# MCU_64.net
KiCad netlist of a schematic drawn in Altium Designer
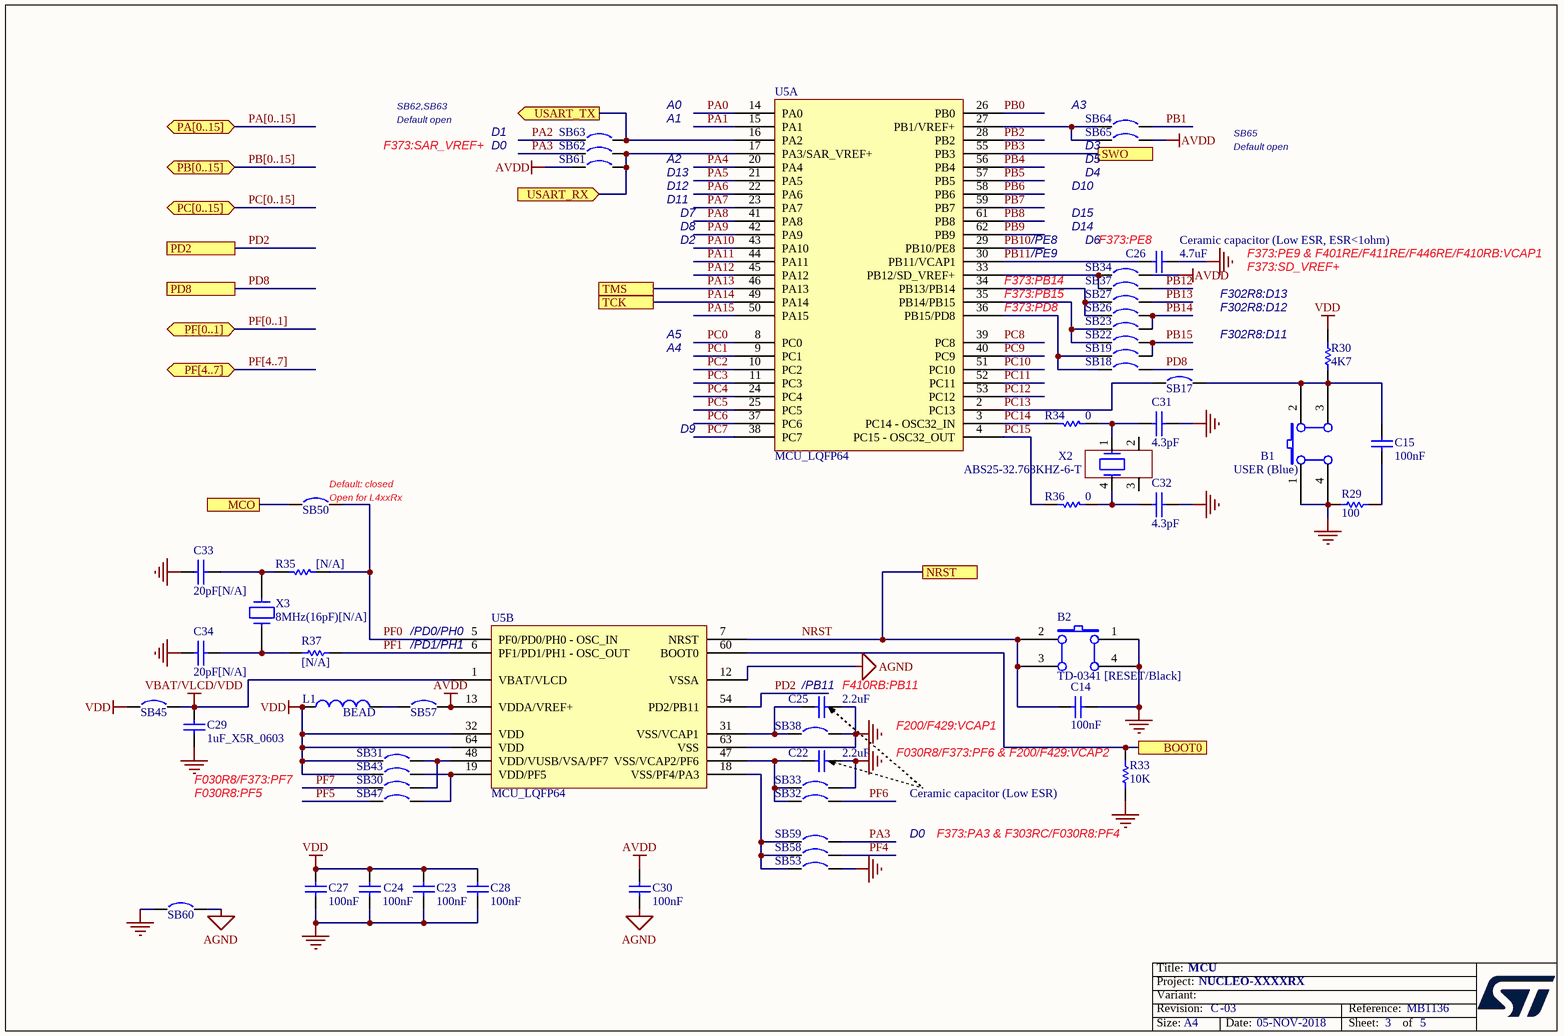
[diagram p0: MCU_64.SchDoc]

(export (version "E")
  (design (tool "Eeschema 10.0.6"))
  (components
    (comp (ref "B1")
      (value "USER (Blue)")
      (footprint "PB10")
      (description "SE PUSHBUTTON")
      (libsource (lib "Documents") (part "SW PUSHBUTTON"))
    )
    (comp (ref "B2")
      (value "TD-0341 [RESET/Black]")
      (footprint "PB10")
      (description "SE PUSHBUTTON")
      (libsource (lib "Documents") (part "SW PUSHBUTTON"))
    )
    (comp (ref "C14")
      (value "100nF")
      (footprint "0603C")
      (description "Capacitor")
      (fields (field (name "PUBLISHER") "Altium Limited"))
      (libsource (lib "Miscellaneous Devices") (part "CAP"))
    )
    (comp (ref "C15")
      (value "100nF")
      (footprint "0603C")
      (description "Capacitor")
      (fields (field (name "PUBLISHER") "Altium Limited"))
      (libsource (lib "Miscellaneous Devices") (part "CAP"))
    )
    (comp (ref "C22")
      (value "2.2uF")
      (footprint "TAN-A")
      (description "Capacitor,2.2uF,16V, X7R,10%,0805,YAGEO")
      (libsource (lib "MCD_TOOLS") (part "Cap_2.2uF_X7R_10%_0805"))
    )
    (comp (ref "C23")
      (value "100nF")
      (footprint "0603C")
      (description "Capacitor")
      (fields (field (name "PUBLISHER") "Altium Limited"))
      (libsource (lib "Miscellaneous Devices") (part "Cap"))
    )
    (comp (ref "C24")
      (value "100nF")
      (footprint "0603C")
      (description "Capacitor")
      (fields (field (name "PUBLISHER") "Altium Limited"))
      (libsource (lib "Miscellaneous Devices") (part "Cap"))
    )
    (comp (ref "C25")
      (value "2.2uF")
      (footprint "TAN-A")
      (description "Capacitor,2.2uF,16V, X7R,10%,0805,YAGEO")
      (libsource (lib "MCD_TOOLS") (part "Cap_2.2uF_X7R_10%_0805"))
    )
    (comp (ref "C26")
      (value "4.7uF")
      (footprint "TAN-A")
      (description "Capacitor,4.7uF,25V, X7R,10%,1206,YAGEO")
      (libsource (lib "MCD_TOOLS") (part "Cap_2.2uF_X7R_10%_0805"))
    )
    (comp (ref "C27")
      (value "100nF")
      (footprint "0603C")
      (description "Capacitor")
      (fields (field (name "PUBLISHER") "Altium Limited"))
      (libsource (lib "Miscellaneous Devices") (part "Cap"))
    )
    (comp (ref "C28")
      (value "100nF")
      (footprint "0603C")
      (description "Capacitor")
      (fields (field (name "PUBLISHER") "Altium Limited"))
      (libsource (lib "Miscellaneous Devices") (part "Cap"))
    )
    (comp (ref "C29")
      (value "1uF_X5R_0603")
      (footprint "0603C")
      (description "0603  X5R 1µF")
      (fields (field (name "TOLERANCE") "10%"))
      (libsource (lib "MB963_1") (part "CAP SMD 0603  X5R 1µF 25V 10%"))
    )
    (comp (ref "C30")
      (value "100nF")
      (footprint "0603C")
      (description "Capacitor")
      (fields (field (name "PUBLISHER") "Altium Limited"))
      (libsource (lib "Miscellaneous Devices") (part "Cap"))
    )
    (comp (ref "C31")
      (value "4.3pF")
      (footprint "0603C")
      (description "Capacitor")
      (libsource (lib "") (part "CAP_1"))
    )
    (comp (ref "C32")
      (value "4.3pF")
      (footprint "0603C")
      (description "Capacitor")
      (libsource (lib "") (part "CAP_1"))
    )
    (comp (ref "C33")
      (value "20pF[N/A]")
      (footprint "0603C")
      (description "Capacitor")
      (libsource (lib "*") (part "CAP"))
    )
    (comp (ref "C34")
      (value "20pF[N/A]")
      (footprint "0603C")
      (description "Capacitor")
      (libsource (lib "*") (part "CAP"))
    )
    (comp (ref "L1")
      (value "BEAD")
      (footprint "0603L")
      (description "Inductor")
      (fields (field (name "PUBLISHER") "Altium Limited"))
      (libsource (lib "Miscellaneous Devices") (part "Inductor"))
    )
    (comp (ref "R29")
      (value "100")
      (footprint "0603R")
      (description "Resistor")
      (fields (field (name "PUBLISHER") "Altium Limited"))
      (libsource (lib "Miscellaneous Devices") (part "Res1"))
    )
    (comp (ref "R30")
      (value "4K7")
      (footprint "0603R")
      (description "Resistor")
      (fields (field (name "PUBLISHER") "Altium Limited"))
      (libsource (lib "Miscellaneous Devices") (part "res1"))
    )
    (comp (ref "R33")
      (value "10K")
      (footprint "0603R")
      (description "Resistor")
      (fields (field (name "PUBLISHER") "Altium Limited"))
      (libsource (lib "Miscellaneous Devices") (part "res1"))
    )
    (comp (ref "R34")
      (value "0")
      (footprint "0603R")
      (description "Resistor")
      (fields (field (name "PUBLISHER") "Altium Limited"))
      (libsource (lib "") (part "Res1_1"))
    )
    (comp (ref "R35")
      (value "[N/A]")
      (footprint "0603R")
      (description "Resistor")
      (fields (field (name "PUBLISHER") "Altium Limited"))
      (libsource (lib "") (part "Res1_1"))
    )
    (comp (ref "R36")
      (value "0")
      (footprint "0603R")
      (description "Resistor")
      (fields (field (name "PUBLISHER") "Altium Limited"))
      (libsource (lib "") (part "Res1_1"))
    )
    (comp (ref "R37")
      (value "[N/A]")
      (footprint "0603R")
      (description "Resistor")
      (fields (field (name "PUBLISHER") "Altium Limited"))
      (libsource (lib "Miscellaneous Devices") (part "Res1"))
    )
    (comp (ref "SB17")
      (value "Circuit Breaker")
      (footprint "JP2_SMD")
      (fields (field (name "PUBLISHER") "Altium Limited"))
      (libsource (lib "MCD_TOOLS") (part "Circuit Breaker"))
    )
    (comp (ref "SB18")
      (value "Circuit Breaker")
      (footprint "JP2_SMD")
      (fields (field (name "PUBLISHER") "Altium Limited"))
      (libsource (lib "MCD_TOOLS") (part "Circuit Breaker"))
    )
    (comp (ref "SB19")
      (value "Circuit Breaker")
      (footprint "JP2_SMD")
      (fields (field (name "PUBLISHER") "Altium Limited"))
      (libsource (lib "MCD_TOOLS") (part "Circuit Breaker"))
    )
    (comp (ref "SB22")
      (value "Circuit Breaker")
      (footprint "JP2_SMD")
      (fields (field (name "PUBLISHER") "Altium Limited"))
      (libsource (lib "MCD_TOOLS") (part "Circuit Breaker"))
    )
    (comp (ref "SB23")
      (value "Circuit Breaker")
      (footprint "JP2_SMD")
      (fields (field (name "PUBLISHER") "Altium Limited"))
      (libsource (lib "MCD_TOOLS") (part "Circuit Breaker"))
    )
    (comp (ref "SB26")
      (value "Circuit Breaker")
      (footprint "JP2_SMD")
      (fields (field (name "PUBLISHER") "Altium Limited"))
      (libsource (lib "MCD_TOOLS") (part "Circuit Breaker"))
    )
    (comp (ref "SB27")
      (value "Circuit Breaker")
      (footprint "JP2_SMD")
      (fields (field (name "PUBLISHER") "Altium Limited"))
      (libsource (lib "MCD_TOOLS") (part "Circuit Breaker"))
    )
    (comp (ref "SB30")
      (value "Circuit Breaker")
      (footprint "JP2_SMD")
      (fields (field (name "PUBLISHER") "Altium Limited"))
      (libsource (lib "MCD_TOOLS") (part "Circuit Breaker"))
    )
    (comp (ref "SB31")
      (value "Circuit Breaker")
      (footprint "JP2_SMD")
      (fields (field (name "PUBLISHER") "Altium Limited"))
      (libsource (lib "MCD_TOOLS") (part "Circuit Breaker"))
    )
    (comp (ref "SB32")
      (value "Circuit Breaker")
      (footprint "JP2_SMD")
      (fields (field (name "PUBLISHER") "Altium Limited"))
      (libsource (lib "MCD_TOOLS") (part "Circuit Breaker"))
    )
    (comp (ref "SB33")
      (value "Circuit Breaker")
      (footprint "JP2_SMD")
      (fields (field (name "PUBLISHER") "Altium Limited"))
      (libsource (lib "MCD_TOOLS") (part "Circuit Breaker"))
    )
    (comp (ref "SB34")
      (value "Circuit Breaker")
      (footprint "JP2_SMD")
      (fields (field (name "PUBLISHER") "Altium Limited"))
      (libsource (lib "MCD_TOOLS") (part "Circuit Breaker"))
    )
    (comp (ref "SB37")
      (value "Circuit Breaker")
      (footprint "JP2_SMD")
      (fields (field (name "PUBLISHER") "Altium Limited"))
      (libsource (lib "MCD_TOOLS") (part "Circuit Breaker"))
    )
    (comp (ref "SB38")
      (value "Circuit Breaker")
      (footprint "JP2_SMD")
      (fields (field (name "PUBLISHER") "Altium Limited"))
      (libsource (lib "MCD_TOOLS") (part "Circuit Breaker"))
    )
    (comp (ref "SB43")
      (value "Circuit Breaker")
      (footprint "JP2_SMD")
      (fields (field (name "PUBLISHER") "Altium Limited"))
      (libsource (lib "MCD_TOOLS") (part "Circuit Breaker"))
    )
    (comp (ref "SB45")
      (value "Circuit Breaker")
      (footprint "JP2_SMD")
      (fields (field (name "PUBLISHER") "Altium Limited"))
      (libsource (lib "MCD_TOOLS") (part "Circuit Breaker"))
    )
    (comp (ref "SB47")
      (value "Circuit Breaker")
      (footprint "JP2_SMD")
      (fields (field (name "PUBLISHER") "Altium Limited"))
      (libsource (lib "MCD_TOOLS") (part "Circuit Breaker"))
    )
    (comp (ref "SB50")
      (value "Circuit Breaker")
      (footprint "JP2_SMD")
      (fields (field (name "PUBLISHER") "Altium Limited"))
      (libsource (lib "MCD_TOOLS") (part "Circuit Breaker"))
    )
    (comp (ref "SB53")
      (value "Circuit Breaker")
      (footprint "JP2_SMD")
      (fields (field (name "PUBLISHER") "Altium Limited"))
      (libsource (lib "MCD_TOOLS") (part "Circuit Breaker"))
    )
    (comp (ref "SB57")
      (value "Circuit Breaker")
      (footprint "JP2_SMD")
      (fields (field (name "PUBLISHER") "Altium Limited"))
      (libsource (lib "MCD_TOOLS") (part "Circuit Breaker"))
    )
    (comp (ref "SB58")
      (value "Circuit Breaker")
      (footprint "JP2_SMD")
      (fields (field (name "PUBLISHER") "Altium Limited"))
      (libsource (lib "MCD_TOOLS") (part "Circuit Breaker"))
    )
    (comp (ref "SB59")
      (value "Circuit Breaker")
      (footprint "JP2_SMD")
      (fields (field (name "PUBLISHER") "Altium Limited"))
      (libsource (lib "MCD_TOOLS") (part "Circuit Breaker"))
    )
    (comp (ref "SB60")
      (value "Circuit Breaker")
      (footprint "JP2_SMD")
      (fields (field (name "PUBLISHER") "Altium Limited"))
      (libsource (lib "MCD_TOOLS") (part "Circuit Breaker"))
    )
    (comp (ref "SB61")
      (value "Circuit Breaker")
      (footprint "JP2_SMD")
      (fields (field (name "PUBLISHER") "Altium Limited"))
      (libsource (lib "MCD_TOOLS") (part "Circuit Breaker"))
    )
    (comp (ref "SB62")
      (value "Circuit Breaker")
      (footprint "JP2_SMD")
      (fields (field (name "PUBLISHER") "Altium Limited"))
      (libsource (lib "MCD_TOOLS") (part "Circuit Breaker"))
    )
    (comp (ref "SB63")
      (value "Circuit Breaker")
      (footprint "JP2_SMD")
      (fields (field (name "PUBLISHER") "Altium Limited"))
      (libsource (lib "MCD_TOOLS") (part "Circuit Breaker"))
    )
    (comp (ref "SB64")
      (value "Circuit Breaker")
      (footprint "JP2_SMD")
      (fields (field (name "PUBLISHER") "Altium Limited"))
      (libsource (lib "MCD_TOOLS") (part "Circuit Breaker"))
    )
    (comp (ref "SB65")
      (value "Circuit Breaker")
      (footprint "JP2_SMD")
      (fields (field (name "PUBLISHER") "Altium Limited"))
      (libsource (lib "MCD_TOOLS") (part "Circuit Breaker"))
    )
    (comp (ref "U5") (value "MCU_LQFP64") (footprint "LQFP64") (libsource (lib "MB1136") (part "MCU_LQFP64")))
    (comp (ref "X2")
      (value "ABS25-32.768KHZ-6-T")
      (footprint "XTAL_4SM_8X3R8")
      (libsource (lib "*") (part "MC306"))
    )
    (comp (ref "X3")
      (value "8MHz(16pF)[N/A]")
      (footprint "XTAL1")
      (description "Crystal")
      (libsource (lib "*") (part "CRYSTAL"))
    )
  )
  (nets
    (net (code "1") (name "/BOOT0") (class "Default")
      (node (ref "R33") (pin "1") (pinfunction "1_1") (pintype "passive"))
      (node (ref "U5") (pin "60") (pinfunction "BOOT0_60") (pintype "passive"))
    )
    (net (code "2") (name "/MCO") (class "Default")
      (node (ref "SB50") (pin "1") (pinfunction "1_1") (pintype "passive"))
    )
    (net (code "3") (name "/NRST") (class "Default")
      (node (ref "B2") (pin "2") (pinfunction "B0_2") (pintype "passive"))
      (node (ref "B2") (pin "3") (pinfunction "B1_3") (pintype "passive"))
      (node (ref "C14") (pin "2") (pinfunction "2_2") (pintype "passive"))
      (node (ref "U5") (pin "7") (pinfunction "NRST_7") (pintype "passive"))
    )
    (net (code "4") (name "/PA0") (class "Default")
      (node (ref "U5") (pin "14") (pinfunction "PA0_14") (pintype "passive"))
    )
    (net (code "5") (name "/PA1") (class "Default")
      (node (ref "U5") (pin "15") (pinfunction "PA1_15") (pintype "passive"))
    )
    (net (code "6") (name "/PA2") (class "Default")
      (node (ref "SB63") (pin "1") (pinfunction "1_1") (pintype "passive"))
    )
    (net (code "7") (name "/PA3") (class "Default")
      (node (ref "SB59") (pin "2") (pinfunction "2_2") (pintype "passive"))
      (node (ref "SB62") (pin "1") (pinfunction "1_1") (pintype "passive"))
    )
    (net (code "8") (name "/PA4") (class "Default")
      (node (ref "U5") (pin "20") (pinfunction "PA4_20") (pintype "passive"))
    )
    (net (code "9") (name "/PA5") (class "Default")
      (node (ref "U5") (pin "21") (pinfunction "PA5_21") (pintype "passive"))
    )
    (net (code "10") (name "/PA6") (class "Default")
      (node (ref "U5") (pin "22") (pinfunction "PA6_22") (pintype "passive"))
    )
    (net (code "11") (name "/PA7") (class "Default")
      (node (ref "U5") (pin "23") (pinfunction "PA7_23") (pintype "passive"))
    )
    (net (code "12") (name "/PA8") (class "Default")
      (node (ref "U5") (pin "41") (pinfunction "PA8_41") (pintype "passive"))
    )
    (net (code "13") (name "/PA9") (class "Default")
      (node (ref "U5") (pin "42") (pinfunction "PA9_42") (pintype "passive"))
    )
    (net (code "14") (name "/PA10") (class "Default")
      (node (ref "U5") (pin "43") (pinfunction "PA10_43") (pintype "passive"))
    )
    (net (code "15") (name "/PA11") (class "Default")
      (node (ref "U5") (pin "44") (pinfunction "PA11_44") (pintype "passive"))
    )
    (net (code "16") (name "/PA12") (class "Default")
      (node (ref "U5") (pin "45") (pinfunction "PA12_45") (pintype "passive"))
    )
    (net (code "17") (name "/PA13") (class "Default")
      (node (ref "U5") (pin "46") (pinfunction "PA13_46") (pintype "passive"))
    )
    (net (code "18") (name "/PA14") (class "Default")
      (node (ref "U5") (pin "49") (pinfunction "PA14_49") (pintype "passive"))
    )
    (net (code "19") (name "/PA15") (class "Default")
      (node (ref "U5") (pin "50") (pinfunction "PA15_50") (pintype "passive"))
    )
    (net (code "21") (name "/PB0") (class "Default")
      (node (ref "U5") (pin "26") (pinfunction "PB0_26") (pintype "passive"))
    )
    (net (code "22") (name "/PB1") (class "Default")
      (node (ref "SB64") (pin "2") (pinfunction "2_2") (pintype "passive"))
    )
    (net (code "23") (name "/PB2") (class "Default")
      (node (ref "U5") (pin "28") (pinfunction "PB2_28") (pintype "passive"))
    )
    (net (code "24") (name "/PB3") (class "Default")
      (node (ref "U5") (pin "55") (pinfunction "PB3_55") (pintype "passive"))
    )
    (net (code "25") (name "/PB4") (class "Default")
      (node (ref "U5") (pin "56") (pinfunction "PB4_56") (pintype "passive"))
    )
    (net (code "26") (name "/PB5") (class "Default")
      (node (ref "U5") (pin "57") (pinfunction "PB5_57") (pintype "passive"))
    )
    (net (code "27") (name "/PB6") (class "Default")
      (node (ref "U5") (pin "58") (pinfunction "PB6_58") (pintype "passive"))
    )
    (net (code "28") (name "/PB7") (class "Default")
      (node (ref "U5") (pin "59") (pinfunction "PB7_59") (pintype "passive"))
    )
    (net (code "29") (name "/PB8") (class "Default")
      (node (ref "U5") (pin "61") (pinfunction "PB8_61") (pintype "passive"))
    )
    (net (code "30") (name "/PB9") (class "Default")
      (node (ref "U5") (pin "62") (pinfunction "PB9_62") (pintype "passive"))
    )
    (net (code "31") (name "/PB10") (class "Default")
      (node (ref "U5") (pin "29") (pinfunction "PB10/PE8_29") (pintype "passive"))
    )
    (net (code "32") (name "/PB11") (class "Default")
      (node (ref "C26") (pin "1") (pinfunction "1_1") (pintype "passive"))
      (node (ref "U5") (pin "30") (pinfunction "PB11/VCAP1_30") (pintype "passive"))
    )
    (net (code "33") (name "/PB12") (class "Default")
      (node (ref "SB37") (pin "2") (pinfunction "2_2") (pintype "passive"))
    )
    (net (code "34") (name "/PB13") (class "Default")
      (node (ref "SB27") (pin "2") (pinfunction "2_2") (pintype "passive"))
    )
    (net (code "35") (name "/PB14") (class "Default")
      (node (ref "SB23") (pin "2") (pinfunction "2_2") (pintype "passive"))
      (node (ref "SB26") (pin "2") (pinfunction "2_2") (pintype "passive"))
    )
    (net (code "36") (name "/PB15") (class "Default")
      (node (ref "SB19") (pin "2") (pinfunction "2_2") (pintype "passive"))
      (node (ref "SB22") (pin "2") (pinfunction "2_2") (pintype "passive"))
    )
    (net (code "38") (name "/PC0") (class "Default")
      (node (ref "U5") (pin "8") (pinfunction "PC0_8") (pintype "passive"))
    )
    (net (code "39") (name "/PC1") (class "Default")
      (node (ref "U5") (pin "9") (pinfunction "PC1_9") (pintype "passive"))
    )
    (net (code "40") (name "/PC2") (class "Default")
      (node (ref "U5") (pin "10") (pinfunction "PC2_10") (pintype "passive"))
    )
    (net (code "41") (name "/PC3") (class "Default")
      (node (ref "U5") (pin "11") (pinfunction "PC3_11") (pintype "passive"))
    )
    (net (code "42") (name "/PC4") (class "Default")
      (node (ref "U5") (pin "24") (pinfunction "PC4_24") (pintype "passive"))
    )
    (net (code "43") (name "/PC5") (class "Default")
      (node (ref "U5") (pin "25") (pinfunction "PC5_25") (pintype "passive"))
    )
    (net (code "44") (name "/PC6") (class "Default")
      (node (ref "U5") (pin "37") (pinfunction "PC6_37") (pintype "passive"))
    )
    (net (code "45") (name "/PC7") (class "Default")
      (node (ref "U5") (pin "38") (pinfunction "PC7_38") (pintype "passive"))
    )
    (net (code "46") (name "/PC8") (class "Default")
      (node (ref "U5") (pin "39") (pinfunction "PC8_39") (pintype "passive"))
    )
    (net (code "47") (name "/PC9") (class "Default")
      (node (ref "U5") (pin "40") (pinfunction "PC9_40") (pintype "passive"))
    )
    (net (code "48") (name "/PC10") (class "Default")
      (node (ref "U5") (pin "51") (pinfunction "PC10_51") (pintype "passive"))
    )
    (net (code "49") (name "/PC11") (class "Default")
      (node (ref "U5") (pin "52") (pinfunction "PC11_52") (pintype "passive"))
    )
    (net (code "50") (name "/PC12") (class "Default")
      (node (ref "U5") (pin "53") (pinfunction "PC12_53") (pintype "passive"))
    )
    (net (code "51") (name "/PC13") (class "Default")
      (node (ref "SB17") (pin "1") (pinfunction "1_1") (pintype "passive"))
      (node (ref "U5") (pin "2") (pinfunction "PC13_2") (pintype "passive"))
    )
    (net (code "52") (name "/PC14") (class "Default")
      (node (ref "R34") (pin "2") (pinfunction "2_2") (pintype "passive"))
      (node (ref "U5") (pin "3") (pinfunction "PC14_-_OSC32_IN_3") (pintype "passive"))
    )
    (net (code "53") (name "/PC15") (class "Default")
      (node (ref "R36") (pin "2") (pinfunction "2_2") (pintype "passive"))
      (node (ref "U5") (pin "4") (pinfunction "PC15_-_OSC32_OUT_4") (pintype "passive"))
    )
    (net (code "55") (name "/PD2") (class "Default")
      (node (ref "U5") (pin "54") (pinfunction "PD2/PB11_54") (pintype "passive"))
    )
    (net (code "56") (name "/PD8") (class "Default")
      (node (ref "SB18") (pin "2") (pinfunction "2_2") (pintype "passive"))
    )
    (net (code "57") (name "/PF0") (class "Default")
      (node (ref "R35") (pin "1") (pinfunction "1_1") (pintype "passive"))
      (node (ref "SB50") (pin "2") (pinfunction "2_2") (pintype "passive"))
      (node (ref "U5") (pin "5") (pinfunction "PF0/PD0/PH0_-_OSC_IN_5") (pintype "passive"))
    )
    (net (code "58") (name "/PF1") (class "Default")
      (node (ref "R37") (pin "1") (pinfunction "1_1") (pintype "passive"))
      (node (ref "U5") (pin "6") (pinfunction "PF1/PD1/PH1_-_OSC_OUT_6") (pintype "passive"))
    )
    (net (code "59") (name "/PF4") (class "Default")
      (node (ref "SB58") (pin "2") (pinfunction "2_2") (pintype "passive"))
    )
    (net (code "60") (name "/PF5") (class "Default")
      (node (ref "SB47") (pin "1") (pinfunction "1_1") (pintype "passive"))
    )
    (net (code "61") (name "/PF6") (class "Default")
      (node (ref "SB32") (pin "2") (pinfunction "2_2") (pintype "passive"))
    )
    (net (code "62") (name "/PF7") (class "Default")
      (node (ref "SB30") (pin "1") (pinfunction "1_1") (pintype "passive"))
    )
    (net (code "65") (name "/USART_RX") (class "Default")
      (node (ref "SB61") (pin "2") (pinfunction "2_2") (pintype "passive"))
      (node (ref "SB62") (pin "2") (pinfunction "2_2") (pintype "passive"))
      (node (ref "U5") (pin "17") (pinfunction "PA3/SAR_VREF+_17") (pintype "passive"))
    )
    (net (code "66") (name "/USART_TX") (class "Default")
      (node (ref "SB63") (pin "2") (pinfunction "2_2") (pintype "passive"))
      (node (ref "U5") (pin "16") (pinfunction "PA2_16") (pintype "passive"))
    )
    (net (code "67") (name "AGND") (class "Default")
      (node (ref "C30") (pin "2") (pinfunction "2_2") (pintype "passive"))
      (node (ref "SB60") (pin "2") (pinfunction "2_2") (pintype "passive"))
      (node (ref "U5") (pin "12") (pinfunction "VSSA_12") (pintype "passive"))
    )
    (net (code "68") (name "AVDD") (class "Default")
      (node (ref "C30") (pin "1") (pinfunction "1_1") (pintype "passive"))
      (node (ref "SB34") (pin "2") (pinfunction "2_2") (pintype "passive"))
      (node (ref "SB57") (pin "2") (pinfunction "2_2") (pintype "passive"))
      (node (ref "SB61") (pin "1") (pinfunction "1_1") (pintype "passive"))
      (node (ref "SB65") (pin "2") (pinfunction "2_2") (pintype "passive"))
      (node (ref "U5") (pin "13") (pinfunction "VDDA/VREF+_13") (pintype "passive"))
    )
    (net (code "69") (name "GND") (class "Default")
      (node (ref "B1") (pin "1") (pinfunction "A0_1") (pintype "passive"))
      (node (ref "B1") (pin "4") (pinfunction "A1_4") (pintype "passive"))
      (node (ref "B2") (pin "1") (pinfunction "A0_1") (pintype "passive"))
      (node (ref "B2") (pin "4") (pinfunction "A1_4") (pintype "passive"))
      (node (ref "C14") (pin "1") (pinfunction "1_1") (pintype "passive"))
      (node (ref "C22") (pin "2") (pinfunction "2_2") (pintype "passive"))
      (node (ref "C23") (pin "2") (pinfunction "2_2") (pintype "passive"))
      (node (ref "C24") (pin "2") (pinfunction "2_2") (pintype "passive"))
      (node (ref "C25") (pin "2") (pinfunction "2_2") (pintype "passive"))
      (node (ref "C26") (pin "2") (pinfunction "2_2") (pintype "passive"))
      (node (ref "C27") (pin "2") (pinfunction "2_2") (pintype "passive"))
      (node (ref "C28") (pin "2") (pinfunction "2_2") (pintype "passive"))
      (node (ref "C29") (pin "2") (pinfunction "2_2") (pintype "passive"))
      (node (ref "C31") (pin "2") (pinfunction "2_2") (pintype "passive"))
      (node (ref "C32") (pin "2") (pinfunction "2_2") (pintype "passive"))
      (node (ref "C33") (pin "2") (pinfunction "2_2") (pintype "passive"))
      (node (ref "C34") (pin "2") (pinfunction "2_2") (pintype "passive"))
      (node (ref "R29") (pin "1") (pinfunction "1_1") (pintype "passive"))
      (node (ref "R33") (pin "2") (pinfunction "2_2") (pintype "passive"))
      (node (ref "SB33") (pin "2") (pinfunction "2_2") (pintype "passive"))
      (node (ref "SB38") (pin "2") (pinfunction "2_2") (pintype "passive"))
      (node (ref "SB53") (pin "2") (pinfunction "2_2") (pintype "passive"))
      (node (ref "SB60") (pin "1") (pinfunction "1_1") (pintype "passive"))
      (node (ref "U5") (pin "63") (pinfunction "VSS_63") (pintype "passive"))
    )
    (net (code "70") (name "Net-(B1-B0)") (class "Default")
      (node (ref "B1") (pin "2") (pinfunction "B0_2") (pintype "passive"))
      (node (ref "B1") (pin "3") (pinfunction "B1_3") (pintype "passive"))
      (node (ref "C15") (pin "2") (pinfunction "2_2") (pintype "passive"))
      (node (ref "R30") (pin "1") (pinfunction "1_1") (pintype "passive"))
      (node (ref "SB17") (pin "2") (pinfunction "2_2") (pintype "passive"))
    )
    (net (code "71") (name "Net-(C15-Pad1)") (class "Default")
      (node (ref "C15") (pin "1") (pinfunction "1_1") (pintype "passive"))
      (node (ref "R29") (pin "2") (pinfunction "2_2") (pintype "passive"))
    )
    (net (code "72") (name "Net-(C31-Pad1)") (class "Default")
      (node (ref "C31") (pin "1") (pinfunction "1_1") (pintype "passive"))
      (node (ref "R34") (pin "1") (pinfunction "1_1") (pintype "passive"))
      (node (ref "X2") (pin "1") (pinfunction "1_1") (pintype "passive"))
    )
    (net (code "73") (name "Net-(C32-Pad1)") (class "Default")
      (node (ref "C32") (pin "1") (pinfunction "1_1") (pintype "passive"))
      (node (ref "R36") (pin "1") (pinfunction "1_1") (pintype "passive"))
      (node (ref "X2") (pin "4") (pinfunction "4_4") (pintype "passive"))
    )
    (net (code "74") (name "Net-(C33-Pad1)") (class "Default")
      (node (ref "C33") (pin "1") (pinfunction "1_1") (pintype "passive"))
      (node (ref "R35") (pin "2") (pinfunction "2_2") (pintype "passive"))
      (node (ref "X3") (pin "2") (pinfunction "2_2") (pintype "passive"))
    )
    (net (code "75") (name "Net-(C34-Pad1)") (class "Default")
      (node (ref "C34") (pin "1") (pinfunction "1_1") (pintype "passive"))
      (node (ref "R37") (pin "2") (pinfunction "2_2") (pintype "passive"))
      (node (ref "X3") (pin "1") (pinfunction "1_1") (pintype "passive"))
    )
    (net (code "76") (name "Net-(L1-Pad2)") (class "Default")
      (node (ref "L1") (pin "2") (pinfunction "2_2") (pintype "passive"))
      (node (ref "SB57") (pin "1") (pinfunction "1_1") (pintype "passive"))
    )
    (net (code "77") (name "Net-(U5A-PB1{slash}VREF+)") (class "Default")
      (node (ref "SB64") (pin "1") (pinfunction "1_1") (pintype "passive"))
      (node (ref "SB65") (pin "1") (pinfunction "1_1") (pintype "passive"))
      (node (ref "U5") (pin "27") (pinfunction "PB1/VREF+_27") (pintype "passive"))
    )
    (net (code "78") (name "Net-(U5A-PB12{slash}SD_VREF+)") (class "Default")
      (node (ref "SB34") (pin "1") (pinfunction "1_1") (pintype "passive"))
      (node (ref "SB37") (pin "1") (pinfunction "1_1") (pintype "passive"))
      (node (ref "U5") (pin "33") (pinfunction "PB12/SD_VREF+_33") (pintype "passive"))
    )
    (net (code "79") (name "Net-(U5A-PB13{slash}PB14)") (class "Default")
      (node (ref "SB26") (pin "1") (pinfunction "1_1") (pintype "passive"))
      (node (ref "SB27") (pin "1") (pinfunction "1_1") (pintype "passive"))
      (node (ref "U5") (pin "34") (pinfunction "PB13/PB14_34") (pintype "passive"))
    )
    (net (code "80") (name "Net-(U5A-PB14{slash}PB15)") (class "Default")
      (node (ref "SB22") (pin "1") (pinfunction "1_1") (pintype "passive"))
      (node (ref "SB23") (pin "1") (pinfunction "1_1") (pintype "passive"))
      (node (ref "U5") (pin "35") (pinfunction "PB14/PB15_35") (pintype "passive"))
    )
    (net (code "81") (name "Net-(U5A-PB15{slash}PD8)") (class "Default")
      (node (ref "SB18") (pin "1") (pinfunction "1_1") (pintype "passive"))
      (node (ref "SB19") (pin "1") (pinfunction "1_1") (pintype "passive"))
      (node (ref "U5") (pin "36") (pinfunction "PB15/PD8_36") (pintype "passive"))
    )
    (net (code "82") (name "Net-(U5B-VDD{slash}PF5)") (class "Default")
      (node (ref "SB43") (pin "2") (pinfunction "2_2") (pintype "passive"))
      (node (ref "SB47") (pin "2") (pinfunction "2_2") (pintype "passive"))
      (node (ref "U5") (pin "19") (pinfunction "VDD/PF5_19") (pintype "passive"))
    )
    (net (code "83") (name "Net-(U5B-VDD{slash}VUSB{slash}VSA{slash}PF7)") (class "Default")
      (node (ref "SB30") (pin "2") (pinfunction "2_2") (pintype "passive"))
      (node (ref "SB31") (pin "2") (pinfunction "2_2") (pintype "passive"))
      (node (ref "U5") (pin "48") (pinfunction "VDD/VUSB/VSA/PF7_48") (pintype "passive"))
    )
    (net (code "84") (name "Net-(U5B-VSS{slash}PF4{slash}PA3)") (class "Default")
      (node (ref "SB53") (pin "1") (pinfunction "1_1") (pintype "passive"))
      (node (ref "SB58") (pin "1") (pinfunction "1_1") (pintype "passive"))
      (node (ref "SB59") (pin "1") (pinfunction "1_1") (pintype "passive"))
      (node (ref "U5") (pin "18") (pinfunction "VSS/PF4/PA3_18") (pintype "passive"))
    )
    (net (code "85") (name "Net-(U5B-VSS{slash}VCAP1)") (class "Default")
      (node (ref "C25") (pin "1") (pinfunction "1_1") (pintype "passive"))
      (node (ref "SB38") (pin "1") (pinfunction "1_1") (pintype "passive"))
      (node (ref "U5") (pin "31") (pinfunction "VSS/VCAP1_31") (pintype "passive"))
    )
    (net (code "86") (name "Net-(U5B-VSS{slash}VCAP2{slash}PF6)") (class "Default")
      (node (ref "C22") (pin "1") (pinfunction "1_1") (pintype "passive"))
      (node (ref "SB32") (pin "1") (pinfunction "1_1") (pintype "passive"))
      (node (ref "SB33") (pin "1") (pinfunction "1_1") (pintype "passive"))
      (node (ref "U5") (pin "47") (pinfunction "VSS/VCAP2/PF6_47") (pintype "passive"))
    )
    (net (code "87") (name "VBAT{slash}VLCD{slash}VDD") (class "Default")
      (node (ref "C29") (pin "1") (pinfunction "1_1") (pintype "passive"))
      (node (ref "SB45") (pin "2") (pinfunction "2_2") (pintype "passive"))
      (node (ref "U5") (pin "1") (pinfunction "VBAT/VLCD_1") (pintype "passive"))
    )
    (net (code "88") (name "VDD") (class "Default")
      (node (ref "C23") (pin "1") (pinfunction "1_1") (pintype "passive"))
      (node (ref "C24") (pin "1") (pinfunction "1_1") (pintype "passive"))
      (node (ref "C27") (pin "1") (pinfunction "1_1") (pintype "passive"))
      (node (ref "C28") (pin "1") (pinfunction "1_1") (pintype "passive"))
      (node (ref "L1") (pin "1") (pinfunction "1_1") (pintype "passive"))
      (node (ref "R30") (pin "2") (pinfunction "2_2") (pintype "passive"))
      (node (ref "SB31") (pin "1") (pinfunction "1_1") (pintype "passive"))
      (node (ref "SB43") (pin "1") (pinfunction "1_1") (pintype "passive"))
      (node (ref "SB45") (pin "1") (pinfunction "1_1") (pintype "passive"))
      (node (ref "U5") (pin "32") (pinfunction "VDD_32") (pintype "passive"))
      (node (ref "U5") (pin "64") (pinfunction "VDD_64") (pintype "passive"))
    )
    (net (code "89") (name "unconnected-(X2-Pad2)") (class "Default")
      (node (ref "X2") (pin "2") (pinfunction "2_2") (pintype "passive"))
    )
    (net (code "90") (name "unconnected-(X2-Pad3)") (class "Default")
      (node (ref "X2") (pin "3") (pinfunction "3_3") (pintype "passive"))
    )
  )
)
